# STM32.net
KiCad netlist of a schematic drawn in Altium Designer
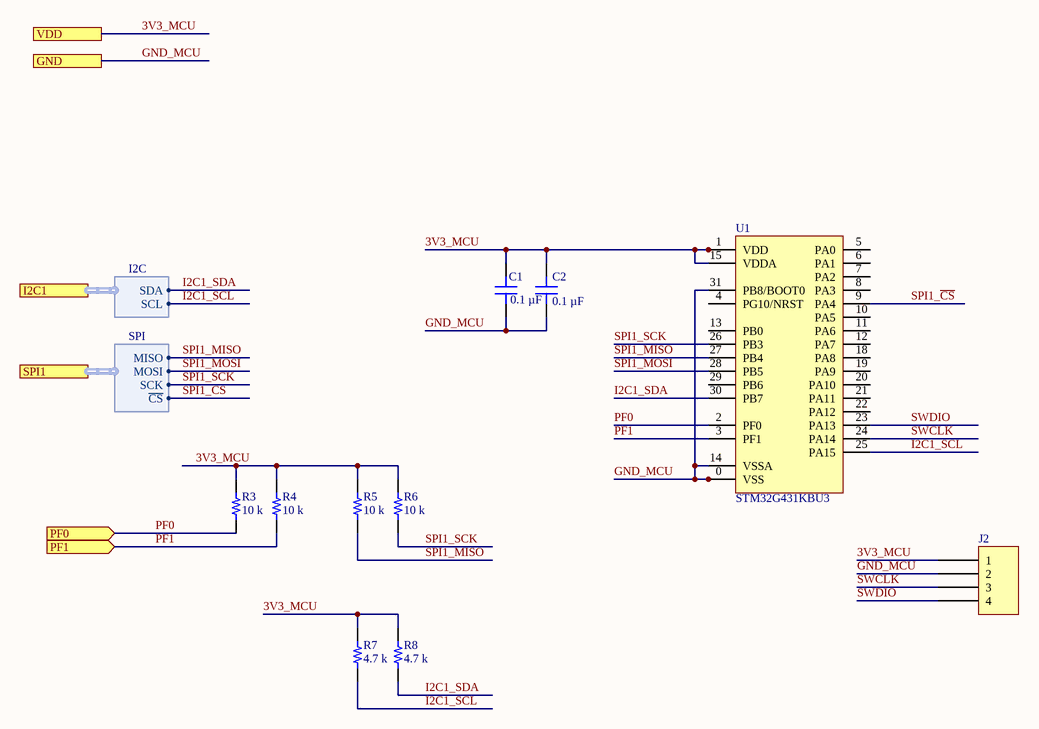
[diagram p0: STM32.SchDoc]

(export (version "E")
  (design (tool "Eeschema 10.0.6"))
  (components
    (comp (ref "C1")
      (value "0.1 µF")
      (footprint "CAP 0402_1005")
      (description "CAP CER 0.1UF 16V X7R 0402")
      (fields (field (name "PART NUMBER") "C0402C104K4RACAUTO") (field (name "MANUFACTURER") "KEMET"))
      (libsource (lib "Celestial Altium Library - altium_library") (part "Capacitor"))
    )
    (comp (ref "C2")
      (value "0.1 µF")
      (footprint "CAP 0402_1005")
      (description "CAP CER 0.1UF 16V X7R 0402")
      (fields (field (name "PART NUMBER") "C0402C104K4RACAUTO") (field (name "MANUFACTURER") "KEMET"))
      (libsource (lib "Celestial Altium Library - altium_library") (part "Capacitor"))
    )
    (comp (ref "J2")
      (value "SM04B-SRSS-TB(LF)(SN)")
      (footprint "JST SM04B-SRSS-TB")
      (description "CONN HEADER SMD R/A 4POS 1MM")
      (fields (field (name "MANUFACTURER") "JST Sales America Inc."))
      (libsource (lib "Celestial Altium Library - altium_library") (part "4 Pin"))
    )
    (comp (ref "R3")
      (value "10 k")
      (footprint "RES 0402_1005")
      (description "RES SMD 10K OHM 0.5% 1/16W 0402")
      (fields (field (name "PART NUMBER") "RT0402DRE0710KL") (field (name "MANUFACTURER") "Yageo"))
      (libsource (lib "Celestial Altium Library - altium_library") (part "Resistor"))
    )
    (comp (ref "R4")
      (value "10 k")
      (footprint "RES 0402_1005")
      (description "RES SMD 10K OHM 0.5% 1/16W 0402")
      (fields (field (name "PART NUMBER") "RT0402DRE0710KL") (field (name "MANUFACTURER") "Yageo"))
      (libsource (lib "Celestial Altium Library - altium_library") (part "Resistor"))
    )
    (comp (ref "R5")
      (value "10 k")
      (footprint "RES 0402_1005")
      (description "RES SMD 10K OHM 0.5% 1/16W 0402")
      (fields (field (name "PART NUMBER") "RT0402DRE0710KL") (field (name "MANUFACTURER") "Yageo"))
      (libsource (lib "Celestial Altium Library - altium_library") (part "Resistor"))
    )
    (comp (ref "R6")
      (value "10 k")
      (footprint "RES 0402_1005")
      (description "RES SMD 10K OHM 0.5% 1/16W 0402")
      (fields (field (name "PART NUMBER") "RT0402DRE0710KL") (field (name "MANUFACTURER") "Yageo"))
      (libsource (lib "Celestial Altium Library - altium_library") (part "Resistor"))
    )
    (comp (ref "R7")
      (value "4.7 k")
      (footprint "RES 0402_1005")
      (description "RES SMD 10K OHM 0.5% 1/16W 0402")
      (fields (field (name "PART NUMBER") "RT0402DRE0710KL") (field (name "MANUFACTURER") "Yageo"))
      (libsource (lib "Celestial Altium Library - altium_library") (part "Resistor"))
    )
    (comp (ref "R8")
      (value "4.7 k")
      (footprint "RES 0402_1005")
      (description "RES SMD 10K OHM 0.5% 1/16W 0402")
      (fields (field (name "PART NUMBER") "RT0402DRE0710KL") (field (name "MANUFACTURER") "Yageo"))
      (libsource (lib "Celestial Altium Library - altium_library") (part "Resistor"))
    )
    (comp (ref "U1")
      (value "STM32G431KBU3")
      (footprint "QFN50P400X400X60-32N")
      (description "MCU UFQFPN-32")
      (libsource (lib "IC") (part "STM32G431KBU3"))
    )
  )
  (nets
    (net (code "3") (name "/3V3_MCU") (class "Default")
      (node (ref "C1") (pin "2") (pinfunction "2_2") (pintype "passive"))
      (node (ref "C2") (pin "2") (pinfunction "2_2") (pintype "passive"))
      (node (ref "J2") (pin "1") (pinfunction "1_1") (pintype "passive"))
      (node (ref "R3") (pin "2") (pinfunction "2_2") (pintype "passive"))
      (node (ref "R4") (pin "2") (pinfunction "2_2") (pintype "passive"))
      (node (ref "R5") (pin "2") (pinfunction "2_2") (pintype "passive"))
      (node (ref "R6") (pin "2") (pinfunction "2_2") (pintype "passive"))
      (node (ref "R7") (pin "2") (pinfunction "2_2") (pintype "passive"))
      (node (ref "R8") (pin "2") (pinfunction "2_2") (pintype "passive"))
      (node (ref "U1") (pin "1") (pinfunction "VDD_1") (pintype "passive"))
      (node (ref "U1") (pin "15") (pinfunction "VDDA_15") (pintype "passive"))
      (node (ref "U1") (pin "17") (pinfunction "VDD_17") (pintype "passive"))
    )
    (net (code "4") (name "/GND_MCU") (class "Default")
      (node (ref "C1") (pin "1") (pinfunction "1_1") (pintype "passive"))
      (node (ref "C2") (pin "1") (pinfunction "1_1") (pintype "passive"))
      (node (ref "J2") (pin "2") (pinfunction "2_2") (pintype "passive"))
      (node (ref "U1") (pin "0") (pinfunction "VSS_0") (pintype "passive"))
      (node (ref "U1") (pin "14") (pinfunction "VSSA_14") (pintype "passive"))
      (node (ref "U1") (pin "16") (pinfunction "VSS_16") (pintype "passive"))
      (node (ref "U1") (pin "31") (pinfunction "PB8/BOOT0_31") (pintype "passive"))
      (node (ref "U1") (pin "32") (pinfunction "VSS_32") (pintype "passive"))
    )
    (net (code "5") (name "/I2C1_SCL") (class "Default")
      (node (ref "R7") (pin "1") (pinfunction "1_1") (pintype "passive"))
      (node (ref "U1") (pin "25") (pinfunction "PA15_25") (pintype "passive"))
    )
    (net (code "6") (name "/I2C1_SDA") (class "Default")
      (node (ref "R8") (pin "1") (pinfunction "1_1") (pintype "passive"))
      (node (ref "U1") (pin "30") (pinfunction "PB7_30") (pintype "passive"))
    )
    (net (code "7") (name "/PF0") (class "Default")
      (node (ref "R3") (pin "1") (pinfunction "1_1") (pintype "passive"))
      (node (ref "U1") (pin "2") (pinfunction "PF0_2") (pintype "passive"))
    )
    (net (code "8") (name "/PF1") (class "Default")
      (node (ref "R4") (pin "1") (pinfunction "1_1") (pintype "passive"))
      (node (ref "U1") (pin "3") (pinfunction "PF1_3") (pintype "passive"))
    )
    (net (code "9") (name "/SPI1_MISO") (class "Default")
      (node (ref "R5") (pin "1") (pinfunction "1_1") (pintype "passive"))
      (node (ref "U1") (pin "27") (pinfunction "PB4_27") (pintype "passive"))
    )
    (net (code "10") (name "/SPI1_MOSI") (class "Default")
      (node (ref "U1") (pin "28") (pinfunction "PB5_28") (pintype "passive"))
    )
    (net (code "11") (name "/SPI1_SCK") (class "Default")
      (node (ref "R6") (pin "1") (pinfunction "1_1") (pintype "passive"))
      (node (ref "U1") (pin "26") (pinfunction "PB3_26") (pintype "passive"))
    )
    (net (code "12") (name "/SPI1_~{CS}") (class "Default")
      (node (ref "U1") (pin "9") (pinfunction "PA4_9") (pintype "passive"))
    )
    (net (code "13") (name "/SWCLK") (class "Default")
      (node (ref "J2") (pin "3") (pinfunction "3_3") (pintype "passive"))
      (node (ref "U1") (pin "24") (pinfunction "PA14_24") (pintype "passive"))
    )
    (net (code "14") (name "/SWDIO") (class "Default")
      (node (ref "J2") (pin "4") (pinfunction "4_4") (pintype "passive"))
      (node (ref "U1") (pin "23") (pinfunction "PA13_23") (pintype "passive"))
    )
    (net (code "17") (name "unconnected-(U1-PA0-Pad5)") (class "Default")
      (node (ref "U1") (pin "5") (pinfunction "PA0_5") (pintype "passive"))
    )
    (net (code "18") (name "unconnected-(U1-PA1-Pad6)") (class "Default")
      (node (ref "U1") (pin "6") (pinfunction "PA1_6") (pintype "passive"))
    )
    (net (code "19") (name "unconnected-(U1-PA2-Pad7)") (class "Default")
      (node (ref "U1") (pin "7") (pinfunction "PA2_7") (pintype "passive"))
    )
    (net (code "20") (name "unconnected-(U1-PA3-Pad8)") (class "Default")
      (node (ref "U1") (pin "8") (pinfunction "PA3_8") (pintype "passive"))
    )
    (net (code "21") (name "unconnected-(U1-PA5-Pad10)") (class "Default")
      (node (ref "U1") (pin "10") (pinfunction "PA5_10") (pintype "passive"))
    )
    (net (code "22") (name "unconnected-(U1-PA6-Pad11)") (class "Default")
      (node (ref "U1") (pin "11") (pinfunction "PA6_11") (pintype "passive"))
    )
    (net (code "23") (name "unconnected-(U1-PA7-Pad12)") (class "Default")
      (node (ref "U1") (pin "12") (pinfunction "PA7_12") (pintype "passive"))
    )
    (net (code "24") (name "unconnected-(U1-PA8-Pad18)") (class "Default")
      (node (ref "U1") (pin "18") (pinfunction "PA8_18") (pintype "passive"))
    )
    (net (code "25") (name "unconnected-(U1-PA9-Pad19)") (class "Default")
      (node (ref "U1") (pin "19") (pinfunction "PA9_19") (pintype "passive"))
    )
    (net (code "26") (name "unconnected-(U1-PA10-Pad20)") (class "Default")
      (node (ref "U1") (pin "20") (pinfunction "PA10_20") (pintype "passive"))
    )
    (net (code "27") (name "unconnected-(U1-PA11-Pad21)") (class "Default")
      (node (ref "U1") (pin "21") (pinfunction "PA11_21") (pintype "passive"))
    )
    (net (code "28") (name "unconnected-(U1-PA12-Pad22)") (class "Default")
      (node (ref "U1") (pin "22") (pinfunction "PA12_22") (pintype "passive"))
    )
    (net (code "29") (name "unconnected-(U1-PB0-Pad13)") (class "Default")
      (node (ref "U1") (pin "13") (pinfunction "PB0_13") (pintype "passive"))
    )
    (net (code "30") (name "unconnected-(U1-PB6-Pad29)") (class "Default")
      (node (ref "U1") (pin "29") (pinfunction "PB6_29") (pintype "passive"))
    )
    (net (code "31") (name "unconnected-(U1-PG10{slash}NRST-Pad4)") (class "Default")
      (node (ref "U1") (pin "4") (pinfunction "PG10/NRST_4") (pintype "passive"))
    )
  )
)
